# harp_behavior_poke_port_breakout_v1_1.net
KiCad netlist of a schematic drawn in EAGLE
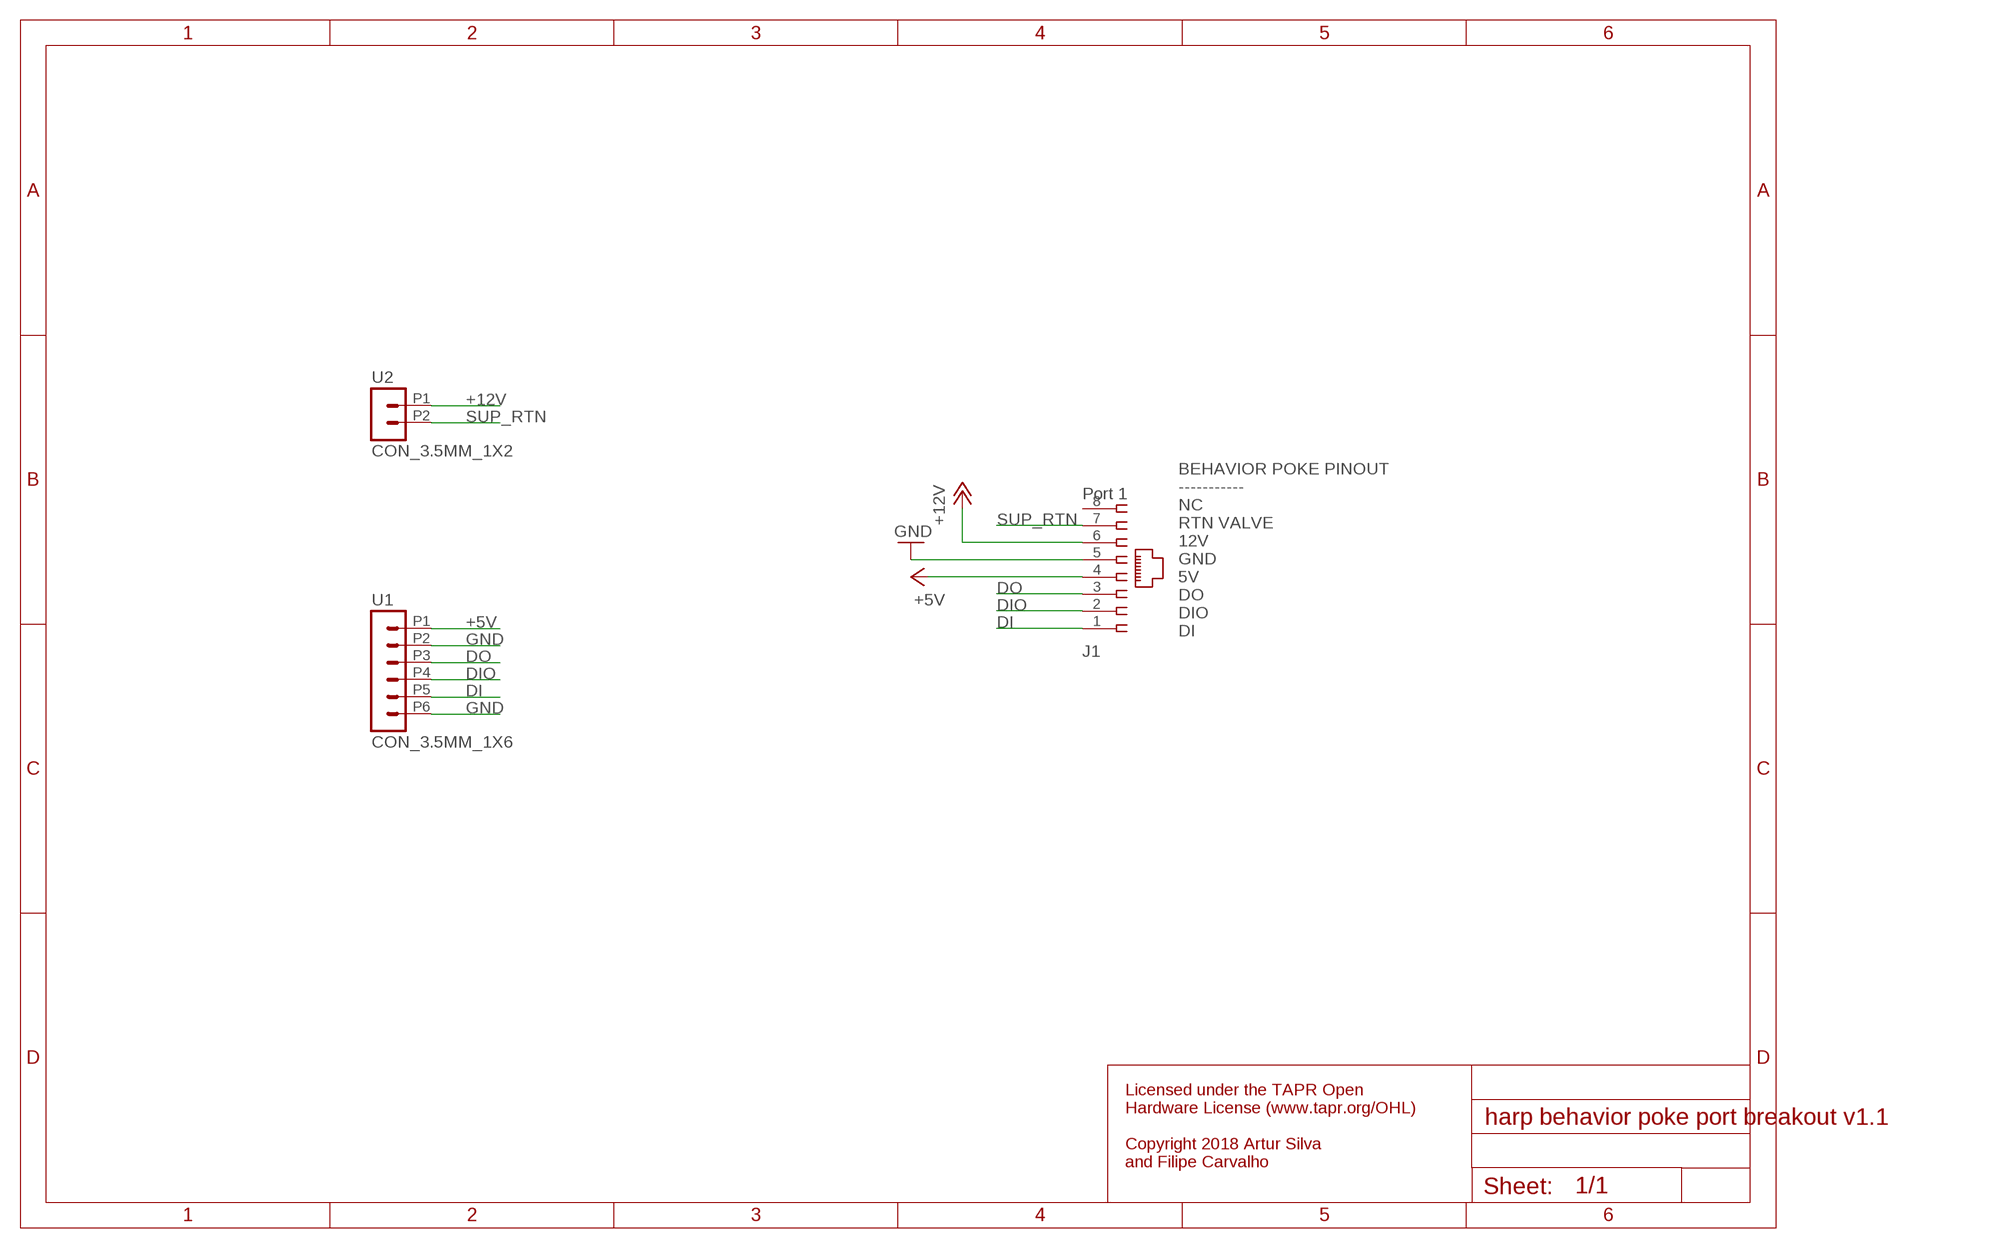
[diagram p0: schematic, sheet 1]

(export (version "E")
  (design (tool "Eeschema 10.0.6"))
  (components
    (comp (ref "J1")
      (value "Port 1")
      (footprint "eagle-import:520426-4")
      (libsource (lib "eagle-import") (part "520426-4"))
    )
    (comp (ref "U1")
      (value "CON_3.5MM_1X6")
      (footprint "eagle-import:CON_3.5MM_1X6")
      (libsource (lib "eagle-import") (part "CON_3.5MM_1X6"))
    )
    (comp (ref "U2")
      (value "CON_3.5MM_1X2")
      (footprint "eagle-import:CON_3.5MM_1X2")
      (libsource (lib "eagle-import") (part "CON_3.5MM_1X2"))
    )
  )
  (nets
    (net (code "1") (name "+5V") (class "Default")
      (node (ref "J1") (pin "4") (pinfunction "4_4") (pintype "passive"))
      (node (ref "U1") (pin "P1") (pinfunction "1_P1") (pintype "passive"))
    )
    (net (code "2") (name "+12V") (class "Default")
      (node (ref "J1") (pin "6") (pinfunction "6_6") (pintype "passive"))
      (node (ref "U2") (pin "P1") (pinfunction "1_P1") (pintype "passive"))
    )
    (net (code "3") (name "/DI") (class "Default")
      (node (ref "J1") (pin "1") (pinfunction "1_1") (pintype "passive"))
      (node (ref "U1") (pin "P5") (pinfunction "5_P5") (pintype "passive"))
    )
    (net (code "4") (name "/DIO") (class "Default")
      (node (ref "J1") (pin "2") (pinfunction "2_2") (pintype "passive"))
      (node (ref "U1") (pin "P4") (pinfunction "4_P4") (pintype "passive"))
    )
    (net (code "5") (name "/DO") (class "Default")
      (node (ref "J1") (pin "3") (pinfunction "3_3") (pintype "passive"))
      (node (ref "U1") (pin "P3") (pinfunction "3_P3") (pintype "passive"))
    )
    (net (code "6") (name "/SUP_RTN") (class "Default")
      (node (ref "J1") (pin "7") (pinfunction "7_7") (pintype "passive"))
      (node (ref "U2") (pin "P2") (pinfunction "2_P2") (pintype "passive"))
    )
    (net (code "7") (name "GND") (class "Default")
      (node (ref "J1") (pin "5") (pinfunction "5_5") (pintype "passive"))
      (node (ref "U1") (pin "P2") (pinfunction "2_P2") (pintype "passive"))
      (node (ref "U1") (pin "P6") (pinfunction "6_P6") (pintype "passive"))
    )
    (net (code "8") (name "unconnected-(J1-Pad8)") (class "Default")
      (node (ref "J1") (pin "8") (pinfunction "8_8") (pintype "passive"))
    )
  )
)
